# 06_LMS7002M_RF2.net
KiCad netlist of a schematic drawn in Altium Designer
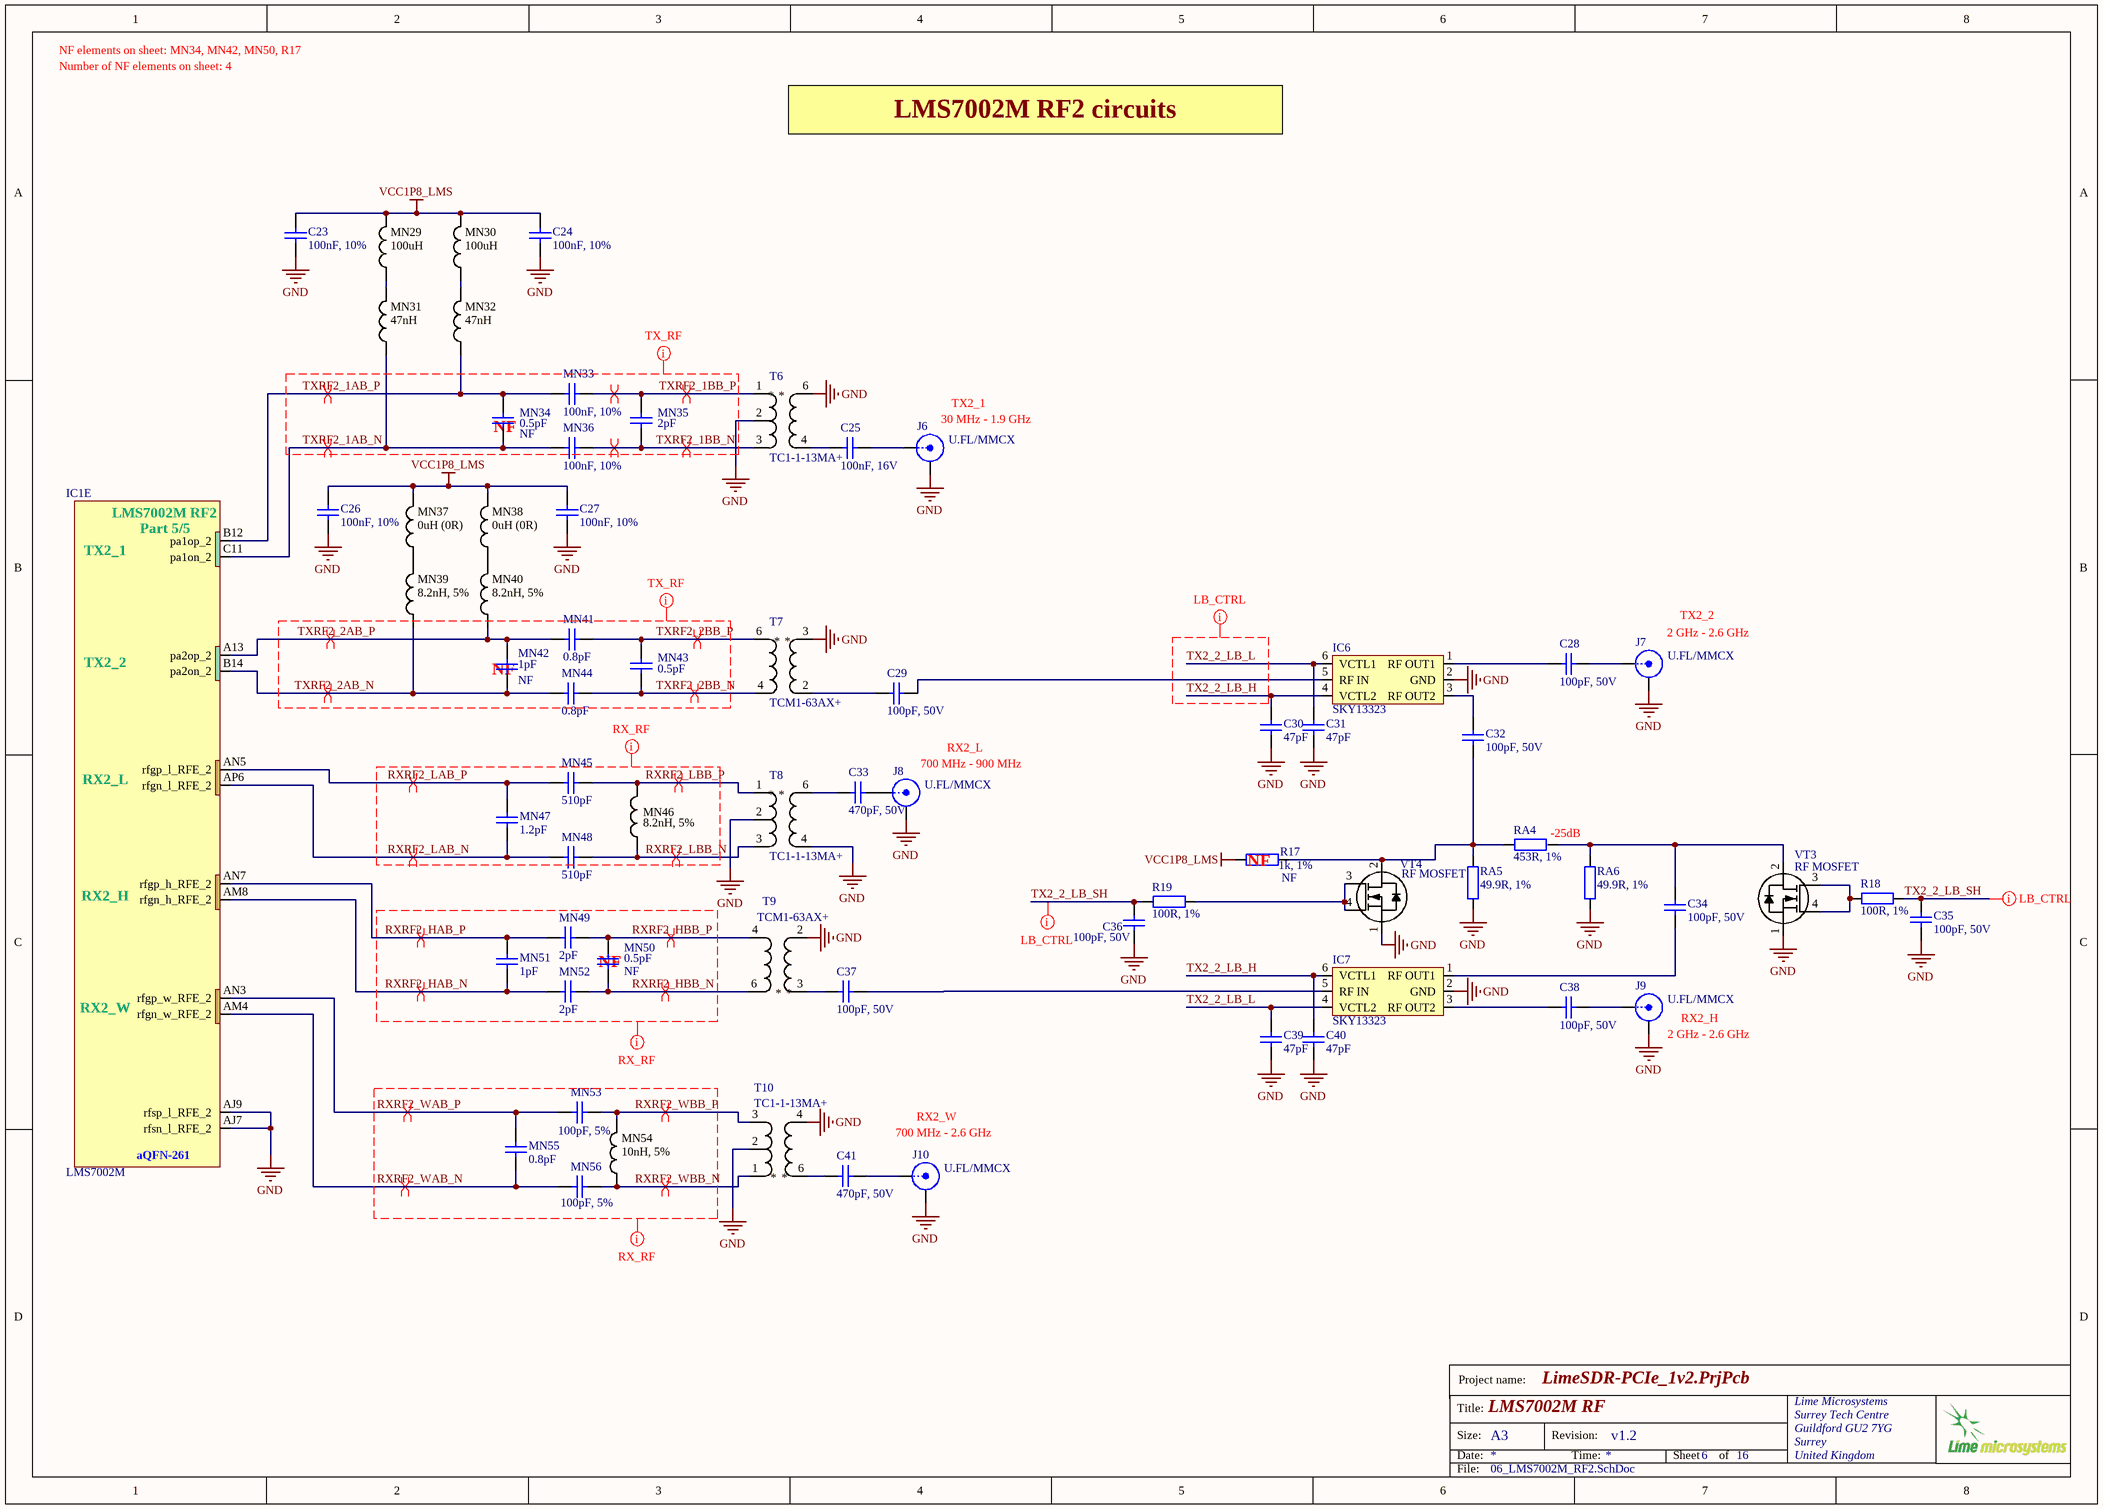
[diagram p0: 06_LMS7002M_RF2.SchDoc]

(export (version "E")
  (design (tool "Eeschema 10.0.6"))
  (components
    (comp (ref "C23")
      (value "100nF, 10%")
      (footprint "CAP0402")
      (fields
        (field (name "MANUFACTURER") "Murata Electronics")
        (field (name "TOLERANCE") "10 %")
        (field (name "MANUFACTURER PART NUMBER") "GRM155R71C104KA88D")
      )
      (libsource (lib "LimeMicroAltiumLib_schLib") (part "Cap_0402"))
    )
    (comp (ref "C24")
      (value "100nF, 10%")
      (footprint "CAP0402")
      (fields
        (field (name "MANUFACTURER") "Murata Electronics")
        (field (name "TOLERANCE") "10 %")
        (field (name "MANUFACTURER PART NUMBER") "GRM155R71C104KA88D")
      )
      (libsource (lib "LimeMicroAltiumLib_schLib") (part "Cap_0402"))
    )
    (comp (ref "C25")
      (value "100nF, 16V")
      (footprint "CAP0402")
      (fields
        (field (name "MANUFACTURER") "Murata Electronics")
        (field (name "TOLERANCE") "10 %")
        (field (name "MANUFACTURER PART NUMBER") "GRM155R71C104KA88D")
      )
      (libsource (lib "LimeMicroAltiumLib_schLib") (part "Cap_0402"))
    )
    (comp (ref "C26")
      (value "100nF, 10%")
      (footprint "CAP0402")
      (fields
        (field (name "MANUFACTURER") "Murata Electronics")
        (field (name "TOLERANCE") "10 %")
        (field (name "MANUFACTURER PART NUMBER") "GRM155R71C104KA88D")
      )
      (libsource (lib "LimeMicroAltiumLib_schLib") (part "Cap_0402"))
    )
    (comp (ref "C27")
      (value "100nF, 10%")
      (footprint "CAP0402")
      (fields
        (field (name "MANUFACTURER") "Murata Electronics")
        (field (name "TOLERANCE") "10 %")
        (field (name "MANUFACTURER PART NUMBER") "GRM155R71C104KA88D")
      )
      (libsource (lib "LimeMicroAltiumLib_schLib") (part "Cap_0402"))
    )
    (comp (ref "C28")
      (value "100pF, 50V")
      (footprint "CAP0402")
      (fields (field (name "TOLERANCE") "±5%") (field (name "MANUFACTURER") "Yageo"))
      (libsource (lib "LimeMicroAltiumLib_schLib") (part "Cap_0402"))
    )
    (comp (ref "C29")
      (value "100pF, 50V")
      (footprint "CAP0402")
      (fields (field (name "TOLERANCE") "±5%") (field (name "MANUFACTURER") "Yageo"))
      (libsource (lib "LimeMicroAltiumLib_schLib") (part "Cap_0402"))
    )
    (comp (ref "C30")
      (value "47pF")
      (footprint "CAP0402")
      (fields (field (name "TOLERANCE") "±1%") (field (name "MANUFACTURER") "TDK Corporation"))
      (libsource (lib "LimeMicroAltiumLib_schLib") (part "Cap_0402"))
    )
    (comp (ref "C31")
      (value "47pF")
      (footprint "CAP0402")
      (fields (field (name "TOLERANCE") "±1%") (field (name "MANUFACTURER") "TDK Corporation"))
      (libsource (lib "LimeMicroAltiumLib_schLib") (part "Cap_0402"))
    )
    (comp (ref "C32")
      (value "100pF, 50V")
      (footprint "CAP0402")
      (fields (field (name "TOLERANCE") "±5%") (field (name "MANUFACTURER") "Yageo"))
      (libsource (lib "LimeMicroAltiumLib_schLib") (part "Cap_0402"))
    )
    (comp (ref "C33")
      (value "470pF, 50V")
      (footprint "CAP0402")
      (fields
        (field (name "MANUFACTURER PART NUMBER") "C1005C0G1H471J050BA")
        (field (name "TOLERANCE") "±5%")
        (field (name "MANUFACTURER") "TDK Corporation")
      )
      (libsource (lib "LimeMicroAltiumLib_schLib") (part "Cap_0402"))
    )
    (comp (ref "C34")
      (value "100pF, 50V")
      (footprint "CAP0402")
      (fields (field (name "TOLERANCE") "±5%") (field (name "MANUFACTURER") "Yageo"))
      (libsource (lib "LimeMicroAltiumLib_schLib") (part "Cap_0402"))
    )
    (comp (ref "C35")
      (value "100pF, 50V")
      (footprint "CAP0402")
      (fields (field (name "TOLERANCE") "±5%") (field (name "MANUFACTURER") "Yageo"))
      (libsource (lib "LimeMicroAltiumLib_schLib") (part "Cap_0402"))
    )
    (comp (ref "C36")
      (value "100pF, 50V")
      (footprint "CAP0402")
      (fields (field (name "TOLERANCE") "±5%") (field (name "MANUFACTURER") "Yageo"))
      (libsource (lib "LimeMicroAltiumLib_schLib") (part "Cap_0402"))
    )
    (comp (ref "C37")
      (value "100pF, 50V")
      (footprint "CAP0402")
      (fields (field (name "TOLERANCE") "±5%") (field (name "MANUFACTURER") "Yageo"))
      (libsource (lib "LimeMicroAltiumLib_schLib") (part "Cap_0402"))
    )
    (comp (ref "C38")
      (value "100pF, 50V")
      (footprint "CAP0402")
      (fields (field (name "TOLERANCE") "±5%") (field (name "MANUFACTURER") "Yageo"))
      (libsource (lib "LimeMicroAltiumLib_schLib") (part "Cap_0402"))
    )
    (comp (ref "C39")
      (value "47pF")
      (footprint "CAP0402")
      (fields (field (name "TOLERANCE") "±1%") (field (name "MANUFACTURER") "TDK Corporation"))
      (libsource (lib "LimeMicroAltiumLib_schLib") (part "Cap_0402"))
    )
    (comp (ref "C40")
      (value "47pF")
      (footprint "CAP0402")
      (fields (field (name "TOLERANCE") "±1%") (field (name "MANUFACTURER") "TDK Corporation"))
      (libsource (lib "LimeMicroAltiumLib_schLib") (part "Cap_0402"))
    )
    (comp (ref "C41")
      (value "470pF, 50V")
      (footprint "CAP0402")
      (fields
        (field (name "MANUFACTURER PART NUMBER") "C1005C0G1H471J050BA")
        (field (name "TOLERANCE") "±5%")
        (field (name "MANUFACTURER") "TDK Corporation")
      )
      (libsource (lib "LimeMicroAltiumLib_schLib") (part "Cap_0402"))
    )
    (comp (ref "IC1")
      (value "LMS7002M")
      (footprint "LMS7002M_v2")
      (fields (field (name "MANUFACTURER") "Lime Microsystems"))
      (libsource (lib "LimeMicroAltiumLib_schLib") (part "LMS7002M"))
    )
    (comp (ref "IC6")
      (value "SKY13323")
      (footprint "SKY13323-378LF")
      (description "SKY13323-378LF: 0.1-3.0 GHz GaAs SPDT Switch")
      (fields (field (name "MANUFACTURER") "Skyworks Solutions Inc."))
      (libsource (lib "LimeMicroAltiumLib_schLib") (part "SKY13323"))
    )
    (comp (ref "IC7")
      (value "SKY13323")
      (footprint "SKY13323-378LF")
      (description "SKY13323-378LF: 0.1-3.0 GHz GaAs SPDT Switch")
      (fields (field (name "MANUFACTURER") "Skyworks Solutions Inc."))
      (libsource (lib "LimeMicroAltiumLib_schLib") (part "SKY13323"))
    )
    (comp (ref "J6")
      (value "U.FL/MMCX")
      (footprint "MMCX_UFL_conn_u")
      (description "CONN UMC RCPT STR 50 OHM SMD")
      (fields (field (name "MANUFACTURER") "Molex, LLC"))
      (libsource (lib "LimeMicroAltiumLib_schLib") (part "RF_IF_connector"))
    )
    (comp (ref "J7")
      (value "U.FL/MMCX")
      (footprint "MMCX_UFL_conn_u")
      (description "CONN UMC RCPT STR 50 OHM SMD")
      (fields (field (name "MANUFACTURER") "Molex, LLC"))
      (libsource (lib "LimeMicroAltiumLib_schLib") (part "RF_IF_connector"))
    )
    (comp (ref "J8")
      (value "U.FL/MMCX")
      (footprint "MMCX_UFL_conn_u")
      (description "CONN UMC RCPT STR 50 OHM SMD")
      (fields (field (name "MANUFACTURER") "Molex, LLC"))
      (libsource (lib "LimeMicroAltiumLib_schLib") (part "RF_IF_connector"))
    )
    (comp (ref "J9")
      (value "U.FL/MMCX")
      (footprint "MMCX_UFL_conn_u")
      (description "CONN UMC RCPT STR 50 OHM SMD")
      (fields (field (name "MANUFACTURER") "Molex, LLC"))
      (libsource (lib "LimeMicroAltiumLib_schLib") (part "RF_IF_connector"))
    )
    (comp (ref "J10")
      (value "U.FL/MMCX")
      (footprint "MMCX_UFL_conn_u")
      (description "CONN UMC RCPT STR 50 OHM SMD")
      (fields (field (name "MANUFACTURER") "Molex, LLC"))
      (libsource (lib "LimeMicroAltiumLib_schLib") (part "RF_IF_connector"))
    )
    (comp (ref "MN29")
      (value "100uH")
      (footprint "RES0805")
      (fields
        (field (name "TOLERANCE") "±10%")
        (field (name "MANUFACTURER") "TDK Corporation")
        (field (name "MANUFACTURER PART NUMBER") "MLF2012C101KT000")
      )
      (libsource (lib "LimeMicroAltiumLib_schLib") (part "Inductor_0603"))
    )
    (comp (ref "MN30")
      (value "100uH")
      (footprint "RES0805")
      (fields
        (field (name "TOLERANCE") "±10%")
        (field (name "MANUFACTURER") "TDK Corporation")
        (field (name "MANUFACTURER PART NUMBER") "MLF2012C101KT000")
      )
      (libsource (lib "LimeMicroAltiumLib_schLib") (part "Inductor_0603"))
    )
    (comp (ref "MN31")
      (value "47nH")
      (footprint "RES0402")
      (fields
        (field (name "MANUFACTURER") "COILCRAFT")
        (field (name "MANUFACTURER PART NUMBER") "0402HP-47NXJLU")
      )
      (libsource (lib "LimeMicroAltiumLib_schLib") (part "Inductor_0603"))
    )
    (comp (ref "MN32")
      (value "47nH")
      (footprint "RES0402")
      (fields
        (field (name "MANUFACTURER") "COILCRAFT")
        (field (name "MANUFACTURER PART NUMBER") "0402HP-47NXJLU")
      )
      (libsource (lib "LimeMicroAltiumLib_schLib") (part "Inductor_0603"))
    )
    (comp (ref "MN33")
      (value "100nF, 10%")
      (footprint "CAP0402")
      (fields
        (field (name "MANUFACTURER") "Murata Electronics")
        (field (name "TOLERANCE") "10 %")
        (field (name "MANUFACTURER PART NUMBER") "GRM155R71C104KA88D")
      )
      (libsource (lib "LimeMicroAltiumLib_schLib") (part "Cap_0402"))
    )
    (comp (ref "MN34")
      (value "0.5pF")
      (footprint "CAP0402")
      (fields
        (field (name "ASSEMBLY INFO") "NF")
        (field (name "TOLERANCE") "±0.25pF")
        (field (name "MANUFACTURER") "Yageo")
      )
      (libsource (lib "LimeMicroAltiumLib_schLib") (part "Cap_0402"))
    )
    (comp (ref "MN35")
      (value "2pF")
      (footprint "CAP0402")
      (fields (field (name "MANUFACTURER PART NUMBER") "04025U2R0BAT2A") (field (name "MANUFACTURER") "AVX"))
      (libsource (lib "LimeMicroAltiumLib_schLib") (part "Cap_0402"))
    )
    (comp (ref "MN36")
      (value "100nF, 10%")
      (footprint "CAP0402")
      (fields
        (field (name "MANUFACTURER") "Murata Electronics")
        (field (name "TOLERANCE") "10 %")
        (field (name "MANUFACTURER PART NUMBER") "GRM155R71C104KA88D")
      )
      (libsource (lib "LimeMicroAltiumLib_schLib") (part "Cap_0402"))
    )
    (comp (ref "MN37")
      (value "0uH (0R)")
      (footprint "RES0805")
      (fields
        (field (name "MANUFACTURER") "BOURNS")
        (field (name "MANUFACTURER PART NUMBER") "CR0805-J/-000ELF")
      )
      (libsource (lib "LimeMicroAltiumLib_schLib") (part "Inductor_0603"))
    )
    (comp (ref "MN38")
      (value "0uH (0R)")
      (footprint "RES0805")
      (fields
        (field (name "MANUFACTURER") "BOURNS")
        (field (name "MANUFACTURER PART NUMBER") "CR0805-J/-000ELF")
      )
      (libsource (lib "LimeMicroAltiumLib_schLib") (part "Inductor_0603"))
    )
    (comp (ref "MN39")
      (value "8.2nH, 5%")
      (footprint "RES0402")
      (fields (field (name "MANUFACTURER") "COILCRAFT"))
      (libsource (lib "LimeMicroAltiumLib_schLib") (part "Inductor_0603"))
    )
    (comp (ref "MN40")
      (value "8.2nH, 5%")
      (footprint "RES0402")
      (fields (field (name "MANUFACTURER") "COILCRAFT"))
      (libsource (lib "LimeMicroAltiumLib_schLib") (part "Inductor_0603"))
    )
    (comp (ref "MN41")
      (value "0.8pF")
      (footprint "CAP0402")
      (fields
        (field (name "TOLERANCE") "±0.1pF")
        (field (name "MANUFACTURER") "Murata Electronics North America")
        (field (name "MANUFACTURER PART NUMBER") "GRM1555C1HR80BA01D")
      )
      (libsource (lib "LimeMicroAltiumLib_schLib") (part "Cap_0402"))
    )
    (comp (ref "MN42")
      (value "1pF")
      (footprint "CAP0402")
      (fields
        (field (name "ASSEMBLY INFO") "NF")
        (field (name "MANUFACTURER") "TDK Corporation")
        (field (name "TOLERANCE") "±0.1pF")
      )
      (libsource (lib "LimeMicroAltiumLib_schLib") (part "Cap_0402"))
    )
    (comp (ref "MN43")
      (value "0.5pF")
      (footprint "CAP0402")
      (fields (field (name "TOLERANCE") "±0.25pF") (field (name "MANUFACTURER") "Yageo"))
      (libsource (lib "LimeMicroAltiumLib_schLib") (part "Cap_0402"))
    )
    (comp (ref "MN44")
      (value "0.8pF")
      (footprint "CAP0402")
      (fields
        (field (name "TOLERANCE") "±0.1pF")
        (field (name "MANUFACTURER") "Murata Electronics North America")
        (field (name "MANUFACTURER PART NUMBER") "GRM1555C1HR80BA01D")
      )
      (libsource (lib "LimeMicroAltiumLib_schLib") (part "Cap_0402"))
    )
    (comp (ref "MN45")
      (value "510pF")
      (footprint "CAP0402")
      (fields
        (field (name "TOLERANCE") "±5%")
        (field (name "MANUFACTURER") "Murata Electronics North America")
        (field (name "MANUFACTURER PART NUMBER") "GRM1555C1H511JA01D")
      )
      (libsource (lib "LimeMicroAltiumLib_schLib") (part "Cap_0402"))
    )
    (comp (ref "MN46")
      (value "8.2nH, 5%")
      (footprint "RES0402")
      (fields (field (name "MANUFACTURER") "COILCRAFT"))
      (libsource (lib "LimeMicroAltiumLib_schLib") (part "Inductor_0603"))
    )
    (comp (ref "MN47")
      (value "1.2pF")
      (footprint "CAP0402")
      (fields
        (field (name "MANUFACTURER") "Murata Electronics North America")
        (field (name "MANUFACTURER PART NUMBER") "GRM1555C1H1R2CA01D")
        (field (name "TOLERANCE") "±0.25pF")
      )
      (libsource (lib "LimeMicroAltiumLib_schLib") (part "Cap_0402"))
    )
    (comp (ref "MN48")
      (value "510pF")
      (footprint "CAP0402")
      (fields
        (field (name "TOLERANCE") "±5%")
        (field (name "MANUFACTURER") "Murata Electronics North America")
        (field (name "MANUFACTURER PART NUMBER") "GRM1555C1H511JA01D")
      )
      (libsource (lib "LimeMicroAltiumLib_schLib") (part "Cap_0402"))
    )
    (comp (ref "MN49")
      (value "2pF")
      (footprint "CAP0402")
      (fields (field (name "MANUFACTURER PART NUMBER") "04025U2R0BAT2A") (field (name "MANUFACTURER") "AVX"))
      (libsource (lib "LimeMicroAltiumLib_schLib") (part "Cap_0402"))
    )
    (comp (ref "MN50")
      (value "0.5pF")
      (footprint "CAP0402")
      (fields
        (field (name "ASSEMBLY INFO") "NF")
        (field (name "TOLERANCE") "±0.25pF")
        (field (name "MANUFACTURER") "Yageo")
      )
      (libsource (lib "LimeMicroAltiumLib_schLib") (part "Cap_0402"))
    )
    (comp (ref "MN51")
      (value "1pF")
      (footprint "CAP0402")
      (fields (field (name "MANUFACTURER") "TDK Corporation") (field (name "TOLERANCE") "±0.1pF"))
      (libsource (lib "LimeMicroAltiumLib_schLib") (part "Cap_0402"))
    )
    (comp (ref "MN52")
      (value "2pF")
      (footprint "CAP0402")
      (fields (field (name "MANUFACTURER PART NUMBER") "04025U2R0BAT2A") (field (name "MANUFACTURER") "AVX"))
      (libsource (lib "LimeMicroAltiumLib_schLib") (part "Cap_0402"))
    )
    (comp (ref "MN53")
      (value "100pF, 5%")
      (footprint "CAP0402")
      (fields (field (name "TOLERANCE") "±5%") (field (name "MANUFACTURER") "Yageo"))
      (libsource (lib "LimeMicroAltiumLib_schLib") (part "Cap_0402"))
    )
    (comp (ref "MN54")
      (value "10nH, 5%")
      (footprint "RES0402")
      (fields (field (name "MANUFACTURER") "COILCRAFT"))
      (libsource (lib "LimeMicroAltiumLib_schLib") (part "Inductor_0603"))
    )
    (comp (ref "MN55")
      (value "0.8pF")
      (footprint "CAP0402")
      (fields
        (field (name "TOLERANCE") "±0.1pF")
        (field (name "MANUFACTURER") "Murata Electronics North America")
        (field (name "MANUFACTURER PART NUMBER") "GRM1555C1HR80BA01D")
      )
      (libsource (lib "LimeMicroAltiumLib_schLib") (part "Cap_0402"))
    )
    (comp (ref "MN56")
      (value "100pF, 5%")
      (footprint "CAP0402")
      (fields (field (name "TOLERANCE") "±5%") (field (name "MANUFACTURER") "Yageo"))
      (libsource (lib "LimeMicroAltiumLib_schLib") (part "Cap_0402"))
    )
    (comp (ref "R17")
      (value "1k, 1%")
      (footprint "RES0402")
      (fields
        (field (name "ASSEMBLY INFO") "NF")
        (field (name "MANUFACTURER") "Stackpole Electronics Inc")
        (field (name "TOLERANCE") "±1%")
      )
      (libsource (lib "LimeMicroAltiumLib_schLib") (part "Res_0402"))
    )
    (comp (ref "R18")
      (value "100R, 1%")
      (footprint "RES0402")
      (fields (field (name "TOLERANCE") "±1%") (field (name "MANUFACTURER") "Stackpole Electronics Inc."))
      (libsource (lib "LimeFPGAboard_schLib") (part "Res_0402"))
    )
    (comp (ref "R19")
      (value "100R, 1%")
      (footprint "RES0402")
      (fields (field (name "TOLERANCE") "±1%") (field (name "MANUFACTURER") "Stackpole Electronics Inc."))
      (libsource (lib "LimeFPGAboard_schLib") (part "Res_0402"))
    )
    (comp (ref "RA4")
      (value "453R, 1%")
      (footprint "RES0402")
      (fields (field (name "MANUFACTURER") "Yageo") (field (name "TOLERANCE") "±1%"))
      (libsource (lib "LimeMicroAltiumLib_schLib") (part "Res_0402"))
    )
    (comp (ref "RA5")
      (value "49.9R, 1%")
      (footprint "RES0402")
      (fields
        (field (name "TOLERANCE") "±1%")
        (field (name "MANUFACTURER") "Samsung Electro-Mechanics America, Inc.")
        (field (name "MANUFACTURER PART NUMBER") "RC1005F49R9CS")
      )
      (libsource (lib "LimeMicroAltiumLib_schLib") (part "Res_0402"))
    )
    (comp (ref "RA6")
      (value "49.9R, 1%")
      (footprint "RES0402")
      (fields
        (field (name "TOLERANCE") "±1%")
        (field (name "MANUFACTURER") "Samsung Electro-Mechanics America, Inc.")
        (field (name "MANUFACTURER PART NUMBER") "RC1005F49R9CS")
      )
      (libsource (lib "LimeMicroAltiumLib_schLib") (part "Res_0402"))
    )
    (comp (ref "T6")
      (value "TC1-1-13MA+")
      (footprint "TC1-1-13MA+_v2")
      (fields (field (name "MANUFACTURER") "Mini-Circuits"))
      (libsource (lib "LimeMicroAltiumLib_schLib") (part "Balun"))
    )
    (comp (ref "T7")
      (value "TCM1-63AX+")
      (footprint "TCM1-63AX+_v2")
      (fields (field (name "MANUFACTURER") "Mini-circuits"))
      (libsource (lib "LimeMicroAltiumLib_schLib") (part "Balun_v2"))
    )
    (comp (ref "T8")
      (value "TC1-1-13MA+")
      (footprint "TC1-1-13MA+_v2")
      (fields (field (name "MANUFACTURER") "Mini-Circuits"))
      (libsource (lib "LimeMicroAltiumLib_schLib") (part "Balun"))
    )
    (comp (ref "T9")
      (value "TCM1-63AX+")
      (footprint "TCM1-63AX+_v2")
      (fields (field (name "MANUFACTURER") "Mini-circuits"))
      (libsource (lib "") (part "Balun_v2_1"))
    )
    (comp (ref "T10")
      (value "TC1-1-13MA+")
      (footprint "TC1-1-13MA+_v2")
      (fields (field (name "MANUFACTURER") "Mini-Circuits"))
      (libsource (lib "") (part "Balun_1"))
    )
    (comp (ref "VT3")
      (value "RF MOSFET")
      (footprint "BF1105R_SOT143R4")
      (fields (field (name "MANUFACTURER") "NXP Semiconductors"))
      (libsource (lib "LimeMicroAltiumLib_schLib") (part "BF1105R,215"))
    )
    (comp (ref "VT4")
      (value "RF MOSFET")
      (footprint "BF1105R_SOT143R4")
      (fields (field (name "MANUFACTURER") "NXP Semiconductors"))
      (libsource (lib "LimeMicroAltiumLib_schLib") (part "BF1105R,215"))
    )
  )
  (nets
    (net (code "1") (name "/RXRF2_HAB_N") (class "Default")
      (node (ref "IC1") (pin "AM8") (pinfunction "rfgn_h_RFE_2_AM8") (pintype "passive"))
      (node (ref "MN51") (pin "1") (pinfunction "1_1") (pintype "passive"))
      (node (ref "MN52") (pin "2") (pinfunction "2_2") (pintype "passive"))
    )
    (net (code "2") (name "/RXRF2_HAB_P") (class "Default")
      (node (ref "IC1") (pin "AN7") (pinfunction "rfgp_h_RFE_2_AN7") (pintype "passive"))
      (node (ref "MN49") (pin "2") (pinfunction "2_2") (pintype "passive"))
      (node (ref "MN51") (pin "2") (pinfunction "2_2") (pintype "passive"))
    )
    (net (code "3") (name "/RXRF2_HBB_N") (class "Default")
      (node (ref "MN50") (pin "1") (pinfunction "1_1") (pintype "passive"))
      (node (ref "MN52") (pin "1") (pinfunction "1_1") (pintype "passive"))
      (node (ref "T9") (pin "6") (pinfunction "6_6") (pintype "passive"))
    )
    (net (code "4") (name "/RXRF2_HBB_P") (class "Default")
      (node (ref "MN49") (pin "1") (pinfunction "1_1") (pintype "passive"))
      (node (ref "MN50") (pin "2") (pinfunction "2_2") (pintype "passive"))
      (node (ref "T9") (pin "4") (pinfunction "4_4") (pintype "passive"))
    )
    (net (code "5") (name "/RXRF2_LAB_N") (class "Default")
      (node (ref "IC1") (pin "AP6") (pinfunction "rfgn_l_RFE_2_AP6") (pintype "passive"))
      (node (ref "MN47") (pin "1") (pinfunction "1_1") (pintype "passive"))
      (node (ref "MN48") (pin "2") (pinfunction "2_2") (pintype "passive"))
    )
    (net (code "6") (name "/RXRF2_LAB_P") (class "Default")
      (node (ref "IC1") (pin "AN5") (pinfunction "rfgp_l_RFE_2_AN5") (pintype "passive"))
      (node (ref "MN45") (pin "2") (pinfunction "2_2") (pintype "passive"))
      (node (ref "MN47") (pin "2") (pinfunction "2_2") (pintype "passive"))
    )
    (net (code "7") (name "/RXRF2_LBB_N") (class "Default")
      (node (ref "MN46") (pin "1") (pinfunction "1_1") (pintype "passive"))
      (node (ref "MN48") (pin "1") (pinfunction "1_1") (pintype "passive"))
      (node (ref "T8") (pin "3") (pinfunction "3_3") (pintype "passive"))
    )
    (net (code "8") (name "/RXRF2_LBB_P") (class "Default")
      (node (ref "MN45") (pin "1") (pinfunction "1_1") (pintype "passive"))
      (node (ref "MN46") (pin "2") (pinfunction "2_2") (pintype "passive"))
      (node (ref "T8") (pin "1") (pinfunction "1_1") (pintype "passive"))
    )
    (net (code "9") (name "/RXRF2_WAB_N") (class "Default")
      (node (ref "IC1") (pin "AM4") (pinfunction "rfgn_w_RFE_2_AM4") (pintype "passive"))
      (node (ref "MN55") (pin "2") (pinfunction "2_2") (pintype "passive"))
      (node (ref "MN56") (pin "2") (pinfunction "2_2") (pintype "passive"))
    )
    (net (code "10") (name "/RXRF2_WAB_P") (class "Default")
      (node (ref "IC1") (pin "AN3") (pinfunction "rfgp_w_RFE_2_AN3") (pintype "passive"))
      (node (ref "MN53") (pin "2") (pinfunction "2_2") (pintype "passive"))
      (node (ref "MN55") (pin "1") (pinfunction "1_1") (pintype "passive"))
    )
    (net (code "11") (name "/RXRF2_WBB_N") (class "Default")
      (node (ref "MN54") (pin "1") (pinfunction "1_1") (pintype "passive"))
      (node (ref "MN56") (pin "1") (pinfunction "1_1") (pintype "passive"))
      (node (ref "T10") (pin "1") (pinfunction "1_1") (pintype "passive"))
    )
    (net (code "12") (name "/RXRF2_WBB_P") (class "Default")
      (node (ref "MN53") (pin "1") (pinfunction "1_1") (pintype "passive"))
      (node (ref "MN54") (pin "2") (pinfunction "2_2") (pintype "passive"))
      (node (ref "T10") (pin "3") (pinfunction "3_3") (pintype "passive"))
    )
    (net (code "13") (name "/TX2_2_LB_H") (class "Default")
      (node (ref "C30") (pin "2") (pinfunction "2_2") (pintype "passive"))
      (node (ref "C40") (pin "2") (pinfunction "2_2") (pintype "passive"))
      (node (ref "IC6") (pin "4") (pinfunction "VCTL2_4") (pintype "input"))
      (node (ref "IC7") (pin "6") (pinfunction "VCTL1_6") (pintype "input"))
    )
    (net (code "14") (name "/TX2_2_LB_L") (class "Default")
      (node (ref "C31") (pin "2") (pinfunction "2_2") (pintype "passive"))
      (node (ref "C39") (pin "2") (pinfunction "2_2") (pintype "passive"))
      (node (ref "IC6") (pin "6") (pinfunction "VCTL1_6") (pintype "input"))
      (node (ref "IC7") (pin "4") (pinfunction "VCTL2_4") (pintype "input"))
    )
    (net (code "15") (name "/TX2_2_LB_SH") (class "Default")
      (node (ref "C35") (pin "1") (pinfunction "1_1") (pintype "passive"))
      (node (ref "C36") (pin "1") (pinfunction "1_1") (pintype "passive"))
      (node (ref "R18") (pin "1") (pinfunction "1_1") (pintype "passive"))
      (node (ref "R19") (pin "2") (pinfunction "2_2") (pintype "passive"))
    )
    (net (code "16") (name "/TXRF2_1AB_N") (class "Default")
      (node (ref "IC1") (pin "C11") (pinfunction "pa1on_2_C11") (pintype "passive"))
      (node (ref "MN31") (pin "1") (pinfunction "1_1") (pintype "passive"))
      (node (ref "MN34") (pin "1") (pinfunction "1_1") (pintype "passive"))
      (node (ref "MN36") (pin "1") (pinfunction "1_1") (pintype "passive"))
    )
    (net (code "17") (name "/TXRF2_1AB_P") (class "Default")
      (node (ref "IC1") (pin "B12") (pinfunction "pa1op_2_B12") (pintype "passive"))
      (node (ref "MN32") (pin "1") (pinfunction "1_1") (pintype "passive"))
      (node (ref "MN33") (pin "2") (pinfunction "2_2") (pintype "passive"))
      (node (ref "MN34") (pin "2") (pinfunction "2_2") (pintype "passive"))
    )
    (net (code "18") (name "/TXRF2_1BB_N") (class "Default")
      (node (ref "MN35") (pin "1") (pinfunction "1_1") (pintype "passive"))
      (node (ref "MN36") (pin "2") (pinfunction "2_2") (pintype "passive"))
      (node (ref "T6") (pin "3") (pinfunction "3_3") (pintype "passive"))
    )
    (net (code "19") (name "/TXRF2_1BB_P") (class "Default")
      (node (ref "MN33") (pin "1") (pinfunction "1_1") (pintype "passive"))
      (node (ref "MN35") (pin "2") (pinfunction "2_2") (pintype "passive"))
      (node (ref "T6") (pin "1") (pinfunction "1_1") (pintype "passive"))
    )
    (net (code "20") (name "/TXRF2_2AB_N") (class "Default")
      (node (ref "IC1") (pin "B14") (pinfunction "pa2on_2_B14") (pintype "passive"))
      (node (ref "MN39") (pin "1") (pinfunction "1_1") (pintype "passive"))
      (node (ref "MN42") (pin "2") (pinfunction "2_2") (pintype "passive"))
      (node (ref "MN44") (pin "2") (pinfunction "2_2") (pintype "passive"))
    )
    (net (code "21") (name "/TXRF2_2AB_P") (class "Default")
      (node (ref "IC1") (pin "A13") (pinfunction "pa2op_2_A13") (pintype "passive"))
      (node (ref "MN40") (pin "1") (pinfunction "1_1") (pintype "passive"))
      (node (ref "MN41") (pin "2") (pinfunction "2_2") (pintype "passive"))
      (node (ref "MN42") (pin "1") (pinfunction "1_1") (pintype "passive"))
    )
    (net (code "22") (name "/TXRF2_2BB_N") (class "Default")
      (node (ref "MN43") (pin "1") (pinfunction "1_1") (pintype "passive"))
      (node (ref "MN44") (pin "1") (pinfunction "1_1") (pintype "passive"))
      (node (ref "T7") (pin "4") (pinfunction "4_4") (pintype "passive"))
    )
    (net (code "23") (name "/TXRF2_2BB_P") (class "Default")
      (node (ref "MN41") (pin "1") (pinfunction "1_1") (pintype "passive"))
      (node (ref "MN43") (pin "2") (pinfunction "2_2") (pintype "passive"))
      (node (ref "T7") (pin "6") (pinfunction "6_6") (pintype "passive"))
    )
    (net (code "24") (name "GND") (class "Default")
      (node (ref "C23") (pin "1") (pinfunction "1_1") (pintype "passive"))
      (node (ref "C24") (pin "1") (pinfunction "1_1") (pintype "passive"))
      (node (ref "C26") (pin "1") (pinfunction "1_1") (pintype "passive"))
      (node (ref "C27") (pin "1") (pinfunction "1_1") (pintype "passive"))
      (node (ref "C30") (pin "1") (pinfunction "1_1") (pintype "passive"))
      (node (ref "C31") (pin "1") (pinfunction "1_1") (pintype "passive"))
      (node (ref "C35") (pin "2") (pinfunction "2_2") (pintype "passive"))
      (node (ref "C36") (pin "2") (pinfunction "2_2") (pintype "passive"))
      (node (ref "C39") (pin "1") (pinfunction "1_1") (pintype "passive"))
      (node (ref "C40") (pin "1") (pinfunction "1_1") (pintype "passive"))
      (node (ref "IC1") (pin "AJ7") (pinfunction "rfsn_l_RFE_2_AJ7") (pintype "passive"))
      (node (ref "IC1") (pin "AJ9") (pinfunction "rfsp_l_RFE_2_AJ9") (pintype "passive"))
      (node (ref "IC6") (pin "2") (pinfunction "GND_2") (pintype "passive"))
      (node (ref "IC7") (pin "2") (pinfunction "GND_2") (pintype "passive"))
      (node (ref "J10") (pin "2") (pinfunction "Y_2") (pintype "passive"))
      (node (ref "J6") (pin "2") (pinfunction "Y_2") (pintype "passive"))
      (node (ref "J7") (pin "2") (pinfunction "Y_2") (pintype "passive"))
      (node (ref "J8") (pin "2") (pinfunction "Y_2") (pintype "passive"))
      (node (ref "J9") (pin "2") (pinfunction "Y_2") (pintype "passive"))
      (node (ref "RA5") (pin "1") (pinfunction "1_1") (pintype "passive"))
      (node (ref "RA6") (pin "1") (pinfunction "1_1") (pintype "passive"))
      (node (ref "T10") (pin "2") (pinfunction "2_2") (pintype "passive"))
      (node (ref "T10") (pin "4") (pinfunction "4_4") (pintype "passive"))
      (node (ref "T6") (pin "2") (pinfunction "2_2") (pintype "passive"))
      (node (ref "T6") (pin "6") (pinfunction "6_6") (pintype "passive"))
      (node (ref "T7") (pin "3") (pinfunction "3_3") (pintype "passive"))
      (node (ref "T8") (pin "2") (pinfunction "2_2") (pintype "passive"))
      (node (ref "T8") (pin "4") (pinfunction "4_4") (pintype "passive"))
      (node (ref "T9") (pin "2") (pinfunction "2_2") (pintype "passive"))
      (node (ref "VT3") (pin "1") (pinfunction "S_1") (pintype "passive"))
      (node (ref "VT4") (pin "1") (pinfunction "S_1") (pintype "passive"))
    )
    (net (code "25") (name "Net-(C25-Pad2)") (class "Default")
      (node (ref "C25") (pin "2") (pinfunction "2_2") (pintype "passive"))
      (node (ref "T6") (pin "4") (pinfunction "4_4") (pintype "passive"))
    )
    (net (code "26") (name "Net-(C29-Pad2)") (class "Default")
      (node (ref "C29") (pin "2") (pinfunction "2_2") (pintype "passive"))
      (node (ref "T7") (pin "2") (pinfunction "2_2") (pintype "passive"))
    )
    (net (code "27") (name "Net-(C33-Pad2)") (class "Default")
      (node (ref "C33") (pin "2") (pinfunction "2_2") (pintype "passive"))
      (node (ref "T8") (pin "6") (pinfunction "6_6") (pintype "passive"))
    )
    (net (code "28") (name "Net-(C37-Pad2)") (class "Default")
      (node (ref "C37") (pin "2") (pinfunction "2_2") (pintype "passive"))
      (node (ref "T9") (pin "3") (pinfunction "3_3") (pintype "passive"))
    )
    (net (code "29") (name "Net-(C41-Pad2)") (class "Default")
      (node (ref "C41") (pin "2") (pinfunction "2_2") (pintype "passive"))
      (node (ref "T10") (pin "6") (pinfunction "6_6") (pintype "passive"))
    )
    (net (code "30") (name "Net-(IC6-RF_IN)") (class "Default")
      (node (ref "C29") (pin "1") (pinfunction "1_1") (pintype "passive"))
      (node (ref "IC6") (pin "5") (pinfunction "RF_IN_5") (pintype "input"))
    )
    (net (code "31") (name "Net-(IC6-RF_OUT1)") (class "Default")
      (node (ref "C28") (pin "2") (pinfunction "2_2") (pintype "passive"))
      (node (ref "IC6") (pin "1") (pinfunction "RF_OUT1_1") (pintype "output"))
    )
    (net (code "32") (name "Net-(IC6-RF_OUT2)") (class "Default")
      (node (ref "C32") (pin "1") (pinfunction "1_1") (pintype "passive"))
      (node (ref "IC6") (pin "3") (pinfunction "RF_OUT2_3") (pintype "output"))
    )
    (net (code "33") (name "Net-(IC7-RF_IN)") (class "Default")
      (node (ref "C37") (pin "1") (pinfunction "1_1") (pintype "passive"))
      (node (ref "IC7") (pin "5") (pinfunction "RF_IN_5") (pintype "input"))
    )
    (net (code "34") (name "Net-(IC7-RF_OUT1)") (class "Default")
      (node (ref "C34") (pin "2") (pinfunction "2_2") (pintype "passive"))
      (node (ref "IC7") (pin "1") (pinfunction "RF_OUT1_1") (pintype "output"))
    )
    (net (code "35") (name "Net-(IC7-RF_OUT2)") (class "Default")
      (node (ref "C38") (pin "2") (pinfunction "2_2") (pintype "passive"))
      (node (ref "IC7") (pin "3") (pinfunction "RF_OUT2_3") (pintype "output"))
    )
    (net (code "36") (name "Net-(J6-X)") (class "Default")
      (node (ref "C25") (pin "1") (pinfunction "1_1") (pintype "passive"))
      (node (ref "J6") (pin "1") (pinfunction "X_1") (pintype "passive"))
    )
    (net (code "37") (name "Net-(J7-X)") (class "Default")
      (node (ref "C28") (pin "1") (pinfunction "1_1") (pintype "passive"))
      (node (ref "J7") (pin "1") (pinfunction "X_1") (pintype "passive"))
    )
    (net (code "38") (name "Net-(J8-X)") (class "Default")
      (node (ref "C33") (pin "1") (pinfunction "1_1") (pintype "passive"))
      (node (ref "J8") (pin "1") (pinfunction "X_1") (pintype "passive"))
    )
    (net (code "39") (name "Net-(J9-X)") (class "Default")
      (node (ref "C38") (pin "1") (pinfunction "1_1") (pintype "passive"))
      (node (ref "J9") (pin "1") (pinfunction "X_1") (pintype "passive"))
    )
    (net (code "40") (name "Net-(J10-X)") (class "Default")
      (node (ref "C41") (pin "1") (pinfunction "1_1") (pintype "passive"))
      (node (ref "J10") (pin "1") (pinfunction "X_1") (pintype "passive"))
    )
    (net (code "41") (name "Net-(MN29-Pad1)") (class "Default")
      (node (ref "MN29") (pin "1") (pinfunction "1_1") (pintype "passive"))
      (node (ref "MN31") (pin "2") (pinfunction "2_2") (pintype "passive"))
    )
    (net (code "42") (name "Net-(MN30-Pad1)") (class "Default")
      (node (ref "MN30") (pin "1") (pinfunction "1_1") (pintype "passive"))
      (node (ref "MN32") (pin "2") (pinfunction "2_2") (pintype "passive"))
    )
    (net (code "43") (name "Net-(MN37-Pad1)") (class "Default")
      (node (ref "MN37") (pin "1") (pinfunction "1_1") (pintype "passive"))
      (node (ref "MN39") (pin "2") (pinfunction "2_2") (pintype "passive"))
    )
    (net (code "44") (name "Net-(MN38-Pad1)") (class "Default")
      (node (ref "MN38") (pin "1") (pinfunction "1_1") (pintype "passive"))
      (node (ref "MN40") (pin "2") (pinfunction "2_2") (pintype "passive"))
    )
    (net (code "45") (name "Net-(VT3-D)") (class "Default")
      (node (ref "C34") (pin "1") (pinfunction "1_1") (pintype "passive"))
      (node (ref "RA4") (pin "2") (pinfunction "2_2") (pintype "passive"))
      (node (ref "RA6") (pin "2") (pinfunction "2_2") (pintype "passive"))
      (node (ref "VT3") (pin "2") (pinfunction "D_2") (pintype "passive"))
    )
    (net (code "46") (name "Net-(VT3-G1)") (class "Default")
      (node (ref "R18") (pin "2") (pinfunction "2_2") (pintype "passive"))
      (node (ref "VT3") (pin "3") (pinfunction "G2_3") (pintype "passive"))
      (node (ref "VT3") (pin "4") (pinfunction "G1_4") (pintype "passive"))
    )
    (net (code "47") (name "Net-(VT4-D)") (class "Default")
      (node (ref "C32") (pin "2") (pinfunction "2_2") (pintype "passive"))
      (node (ref "R17") (pin "1") (pinfunction "1_1") (pintype "passive"))
      (node (ref "RA4") (pin "1") (pinfunction "1_1") (pintype "passive"))
      (node (ref "RA5") (pin "2") (pinfunction "2_2") (pintype "passive"))
      (node (ref "VT4") (pin "2") (pinfunction "D_2") (pintype "passive"))
    )
    (net (code "48") (name "Net-(VT4-G1)") (class "Default")
      (node (ref "R19") (pin "1") (pinfunction "1_1") (pintype "passive"))
      (node (ref "VT4") (pin "3") (pinfunction "G2_3") (pintype "passive"))
      (node (ref "VT4") (pin "4") (pinfunction "G1_4") (pintype "passive"))
    )
    (net (code "49") (name "VCC1P8_LMS") (class "Default")
      (node (ref "C23") (pin "2") (pinfunction "2_2") (pintype "passive"))
      (node (ref "C24") (pin "2") (pinfunction "2_2") (pintype "passive"))
      (node (ref "C26") (pin "2") (pinfunction "2_2") (pintype "passive"))
      (node (ref "C27") (pin "2") (pinfunction "2_2") (pintype "passive"))
      (node (ref "MN29") (pin "2") (pinfunction "2_2") (pintype "passive"))
      (node (ref "MN30") (pin "2") (pinfunction "2_2") (pintype "passive"))
      (node (ref "MN37") (pin "2") (pinfunction "2_2") (pintype "passive"))
      (node (ref "MN38") (pin "2") (pinfunction "2_2") (pintype "passive"))
      (node (ref "R17") (pin "2") (pinfunction "2_2") (pintype "passive"))
    )
  )
)
